# relay_module.net
KiCad netlist of a schematic drawn in EAGLE
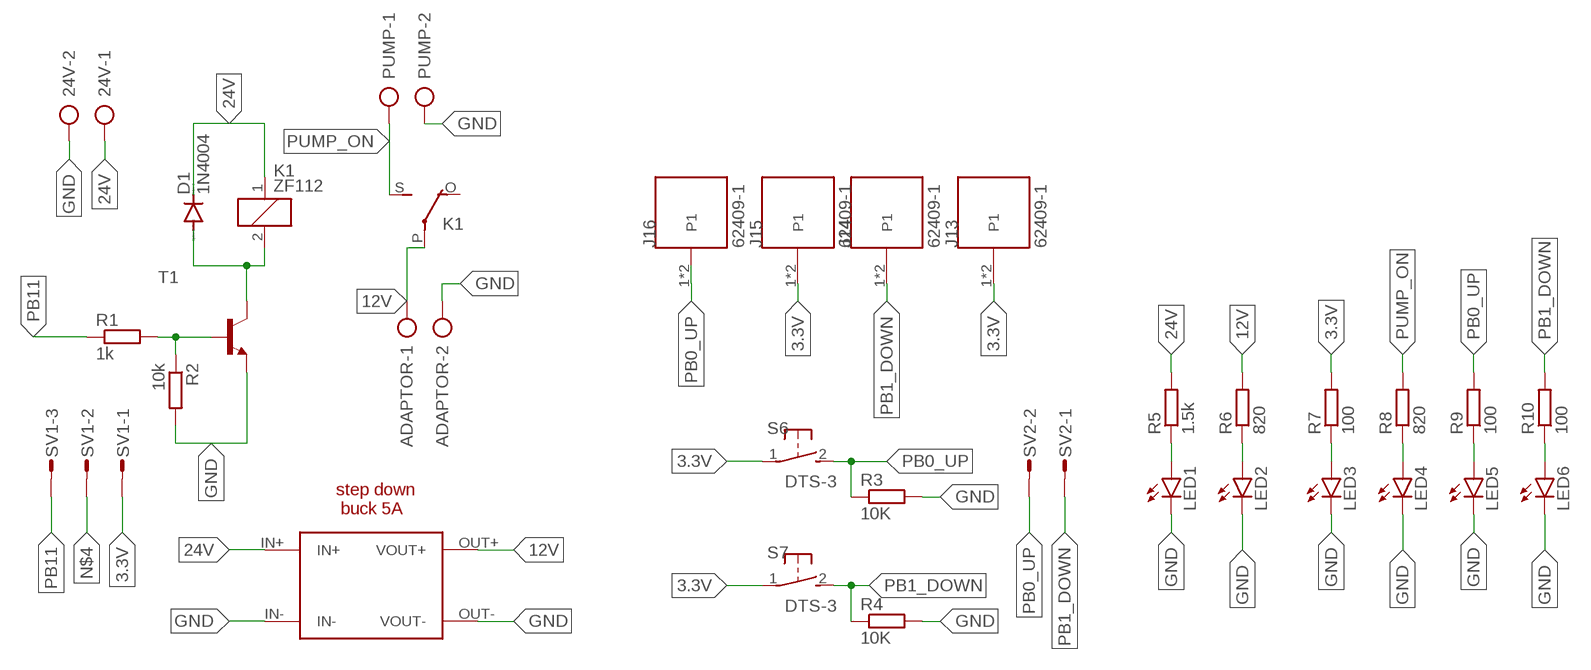
[diagram p0: schematic, sheet 1]

(export (version "E")
  (design (tool "Eeschema 10.0.6"))
  (components
    (comp (ref "24V")
      (value "AK300/2")
      (footprint "eagle-import:AK300_2")
      (libsource (lib "eagle-import") (part "AK300/2"))
    )
    (comp (ref "ADAPTOR")
      (value "AK300/2")
      (footprint "eagle-import:AK300_2")
      (libsource (lib "eagle-import") (part "AK300/2"))
    )
    (comp (ref "D1")
      (value "1N4004")
      (footprint "eagle-import:DO41-10")
      (libsource (lib "eagle-import") (part "1N4004"))
    )
    (comp (ref "J13")
      (value "62409-1")
      (footprint "eagle-import:TE_62409-1")
      (fields (field (name "MF") "TE Connectivity"))
      (libsource (lib "eagle-import") (part "62409-1"))
    )
    (comp (ref "J14")
      (value "62409-1")
      (footprint "eagle-import:TE_62409-1")
      (fields (field (name "MF") "TE Connectivity"))
      (libsource (lib "eagle-import") (part "62409-1"))
    )
    (comp (ref "J15")
      (value "62409-1")
      (footprint "eagle-import:TE_62409-1")
      (fields (field (name "MF") "TE Connectivity"))
      (libsource (lib "eagle-import") (part "62409-1"))
    )
    (comp (ref "J16")
      (value "62409-1")
      (footprint "eagle-import:TE_62409-1")
      (fields (field (name "MF") "TE Connectivity"))
      (libsource (lib "eagle-import") (part "62409-1"))
    )
    (comp (ref "K1")
      (value "ZF112")
      (footprint "eagle-import:ZF112")
      (libsource (lib "eagle-import") (part "ZF112"))
    )
    (comp (ref "LED1")
      (value "LED5MM")
      (footprint "eagle-import:LED5MM")
      (libsource (lib "eagle-import") (part "LED5MM"))
    )
    (comp (ref "LED2")
      (value "LED5MM")
      (footprint "eagle-import:LED5MM")
      (libsource (lib "eagle-import") (part "LED5MM"))
    )
    (comp (ref "LED3")
      (value "LED5MM")
      (footprint "eagle-import:LED5MM")
      (libsource (lib "eagle-import") (part "LED5MM"))
    )
    (comp (ref "LED4")
      (value "LED5MM")
      (footprint "eagle-import:LED5MM")
      (libsource (lib "eagle-import") (part "LED5MM"))
    )
    (comp (ref "LED5")
      (value "LED5MM")
      (footprint "eagle-import:LED5MM")
      (libsource (lib "eagle-import") (part "LED5MM"))
    )
    (comp (ref "LED6")
      (value "LED5MM")
      (footprint "eagle-import:LED5MM")
      (libsource (lib "eagle-import") (part "LED5MM"))
    )
    (comp (ref "PUMP")
      (value "AK300/2")
      (footprint "eagle-import:AK300_2")
      (libsource (lib "eagle-import") (part "AK300/2"))
    )
    (comp (ref "R1")
      (value "1k")
      (footprint "eagle-import:0204_7")
      (libsource (lib "eagle-import") (part "R-EU_0204/7"))
    )
    (comp (ref "R2")
      (value "10k")
      (footprint "eagle-import:0204_7")
      (libsource (lib "eagle-import") (part "R-EU_0204/7"))
    )
    (comp (ref "R3")
      (value "10K")
      (footprint "eagle-import:0204_7")
      (libsource (lib "eagle-import") (part "resistor_348_R-EU_0204/7"))
    )
    (comp (ref "R4")
      (value "10K")
      (footprint "eagle-import:0204_7")
      (libsource (lib "eagle-import") (part "resistor_348_R-EU_0204/7"))
    )
    (comp (ref "R5")
      (value "1.5k")
      (footprint "eagle-import:0204_7")
      (libsource (lib "eagle-import") (part "R-EU_0204/7"))
    )
    (comp (ref "R6")
      (value "820")
      (footprint "eagle-import:0204_7")
      (libsource (lib "eagle-import") (part "R-EU_0204/7"))
    )
    (comp (ref "R7")
      (value "100")
      (footprint "eagle-import:0204_7")
      (libsource (lib "eagle-import") (part "R-EU_0204/7"))
    )
    (comp (ref "R8")
      (value "820")
      (footprint "eagle-import:0204_7")
      (libsource (lib "eagle-import") (part "R-EU_0204/7"))
    )
    (comp (ref "R9")
      (value "100")
      (footprint "eagle-import:0204_7")
      (libsource (lib "eagle-import") (part "R-EU_0204/7"))
    )
    (comp (ref "R10")
      (value "100")
      (footprint "eagle-import:0204_7")
      (libsource (lib "eagle-import") (part "R-EU_0204/7"))
    )
    (comp (ref "S6")
      (value "DTS-3")
      (footprint "eagle-import:DTS-3")
      (libsource (lib "eagle-import") (part "DTS-3"))
    )
    (comp (ref "S7")
      (value "DTS-3")
      (footprint "eagle-import:DTS-3")
      (libsource (lib "eagle-import") (part "DTS-3"))
    )
    (comp (ref "SV1")
      (value "CON-AMP-MT_S03P")
      (footprint "eagle-import:CON-AMP-MT_S03P")
      (libsource (lib "eagle-import") (part "CON-AMP-MT_S03P"))
    )
    (comp (ref "SV2")
      (value "CON-AMP-MT_S02P")
      (footprint "eagle-import:CON-AMP-MT_S02P")
      (libsource (lib "eagle-import") (part "CON-AMP-MT_S02P"))
    )
    (comp (ref "T1")
      (value "2N2222-NPN-TO92-EBC")
      (footprint "eagle-import:TO92-EBC")
      (libsource (lib "eagle-import") (part "-NPN-TO92-EBC2N2222"))
    )
    (comp (ref "U$1")
      (value "BUCK_5A")
      (footprint "eagle-import:BUCK_5A")
      (libsource (lib "eagle-import") (part "BUCK_5A"))
    )
  )
  (nets
    (net (code "1") (name "3.3V") (class "Default")
      (node (ref "J13") (pin "1") (pinfunction "P1_1") (pintype "passive"))
      (node (ref "J13") (pin "2") (pinfunction "P1_2") (pintype "passive"))
      (node (ref "J15") (pin "1") (pinfunction "P1_1") (pintype "passive"))
      (node (ref "J15") (pin "2") (pinfunction "P1_2") (pintype "passive"))
      (node (ref "R7") (pin "2") (pinfunction "2_2") (pintype "passive"))
      (node (ref "S6") (pin "1") (pinfunction "1_1") (pintype "passive"))
      (node (ref "S7") (pin "1") (pinfunction "1_1") (pintype "passive"))
      (node (ref "SV1") (pin "1") (pinfunction "S_1") (pintype "passive"))
    )
    (net (code "2") (name "12V") (class "Default")
      (node (ref "ADAPTOR") (pin "1") (pinfunction "KL_1") (pintype "passive"))
      (node (ref "K1") (pin "P") (pinfunction "P_P") (pintype "passive"))
      (node (ref "R6") (pin "2") (pinfunction "2_2") (pintype "passive"))
      (node (ref "U$1") (pin "OUT+") (pinfunction "VOUT+_OUT+") (pintype "bidirectional"))
    )
    (net (code "3") (name "24V") (class "Default")
      (node (ref "24V") (pin "1") (pinfunction "KL_1") (pintype "passive"))
      (node (ref "D1") (pin "C") (pinfunction "C_C") (pintype "passive"))
      (node (ref "K1") (pin "1") (pinfunction "1_1") (pintype "passive"))
      (node (ref "R5") (pin "2") (pinfunction "2_2") (pintype "passive"))
      (node (ref "U$1") (pin "IN+") (pinfunction "IN+_IN+") (pintype "bidirectional"))
    )
    (net (code "4") (name "GND") (class "Default")
      (node (ref "24V") (pin "2") (pinfunction "KL_2") (pintype "passive"))
      (node (ref "ADAPTOR") (pin "2") (pinfunction "KL_2") (pintype "passive"))
      (node (ref "LED1") (pin "K") (pinfunction "C_K") (pintype "passive"))
      (node (ref "LED2") (pin "K") (pinfunction "C_K") (pintype "passive"))
      (node (ref "LED3") (pin "K") (pinfunction "C_K") (pintype "passive"))
      (node (ref "LED4") (pin "K") (pinfunction "C_K") (pintype "passive"))
      (node (ref "LED5") (pin "K") (pinfunction "C_K") (pintype "passive"))
      (node (ref "LED6") (pin "K") (pinfunction "C_K") (pintype "passive"))
      (node (ref "PUMP") (pin "2") (pinfunction "KL_2") (pintype "passive"))
      (node (ref "R2") (pin "2") (pinfunction "2_2") (pintype "passive"))
      (node (ref "R3") (pin "2") (pinfunction "2_2") (pintype "passive"))
      (node (ref "R4") (pin "2") (pinfunction "2_2") (pintype "passive"))
      (node (ref "T1") (pin "E") (pinfunction "E_E") (pintype "passive"))
      (node (ref "U$1") (pin "IN-") (pinfunction "IN-_IN-") (pintype "bidirectional"))
      (node (ref "U$1") (pin "OUT-") (pinfunction "VOUT-_OUT-") (pintype "bidirectional"))
    )
    (net (code "5") (name "N$4") (class "Default")
      (node (ref "SV1") (pin "2") (pinfunction "S_2") (pintype "passive"))
    )
    (net (code "6") (name "Net-(D1-PadA)") (class "Default")
      (node (ref "D1") (pin "A") (pinfunction "A_A") (pintype "passive"))
      (node (ref "K1") (pin "2") (pinfunction "2_2") (pintype "passive"))
      (node (ref "T1") (pin "C") (pinfunction "C_C") (pintype "passive"))
    )
    (net (code "7") (name "Net-(LED1-PadA)") (class "Default")
      (node (ref "LED1") (pin "A") (pinfunction "A_A") (pintype "passive"))
      (node (ref "R5") (pin "1") (pinfunction "1_1") (pintype "passive"))
    )
    (net (code "8") (name "Net-(LED2-PadA)") (class "Default")
      (node (ref "LED2") (pin "A") (pinfunction "A_A") (pintype "passive"))
      (node (ref "R6") (pin "1") (pinfunction "1_1") (pintype "passive"))
    )
    (net (code "9") (name "Net-(LED3-PadA)") (class "Default")
      (node (ref "LED3") (pin "A") (pinfunction "A_A") (pintype "passive"))
      (node (ref "R7") (pin "1") (pinfunction "1_1") (pintype "passive"))
    )
    (net (code "10") (name "Net-(LED4-PadA)") (class "Default")
      (node (ref "LED4") (pin "A") (pinfunction "A_A") (pintype "passive"))
      (node (ref "R8") (pin "1") (pinfunction "1_1") (pintype "passive"))
    )
    (net (code "11") (name "Net-(LED5-PadA)") (class "Default")
      (node (ref "LED5") (pin "A") (pinfunction "A_A") (pintype "passive"))
      (node (ref "R9") (pin "1") (pinfunction "1_1") (pintype "passive"))
    )
    (net (code "12") (name "Net-(LED6-PadA)") (class "Default")
      (node (ref "LED6") (pin "A") (pinfunction "A_A") (pintype "passive"))
      (node (ref "R10") (pin "1") (pinfunction "1_1") (pintype "passive"))
    )
    (net (code "13") (name "Net-(R1-Pad2)") (class "Default")
      (node (ref "R1") (pin "2") (pinfunction "2_2") (pintype "passive"))
      (node (ref "R2") (pin "1") (pinfunction "1_1") (pintype "passive"))
      (node (ref "T1") (pin "B") (pinfunction "B_B") (pintype "passive"))
    )
    (net (code "14") (name "PB0_UP") (class "Default")
      (node (ref "J16") (pin "1") (pinfunction "P1_1") (pintype "passive"))
      (node (ref "J16") (pin "2") (pinfunction "P1_2") (pintype "passive"))
      (node (ref "R3") (pin "1") (pinfunction "1_1") (pintype "passive"))
      (node (ref "R9") (pin "2") (pinfunction "2_2") (pintype "passive"))
      (node (ref "S6") (pin "2") (pinfunction "2_2") (pintype "passive"))
      (node (ref "SV2") (pin "2") (pinfunction "S_2") (pintype "passive"))
    )
    (net (code "15") (name "PB1_DOWN") (class "Default")
      (node (ref "J14") (pin "1") (pinfunction "P1_1") (pintype "passive"))
      (node (ref "J14") (pin "2") (pinfunction "P1_2") (pintype "passive"))
      (node (ref "R10") (pin "2") (pinfunction "2_2") (pintype "passive"))
      (node (ref "R4") (pin "1") (pinfunction "1_1") (pintype "passive"))
      (node (ref "S7") (pin "2") (pinfunction "2_2") (pintype "passive"))
      (node (ref "SV2") (pin "1") (pinfunction "S_1") (pintype "passive"))
    )
    (net (code "16") (name "PB11") (class "Default")
      (node (ref "R1") (pin "1") (pinfunction "1_1") (pintype "passive"))
      (node (ref "SV1") (pin "3") (pinfunction "S_3") (pintype "passive"))
    )
    (net (code "17") (name "PUMP_ON") (class "Default")
      (node (ref "K1") (pin "S") (pinfunction "S_S") (pintype "passive"))
      (node (ref "PUMP") (pin "1") (pinfunction "KL_1") (pintype "passive"))
      (node (ref "R8") (pin "2") (pinfunction "2_2") (pintype "passive"))
    )
    (net (code "18") (name "unconnected-(K1-PadO)") (class "Default")
      (node (ref "K1") (pin "O") (pinfunction "O_O") (pintype "passive"))
    )
  )
)
